# myPlant.net
KiCad netlist of a schematic drawn in EAGLE
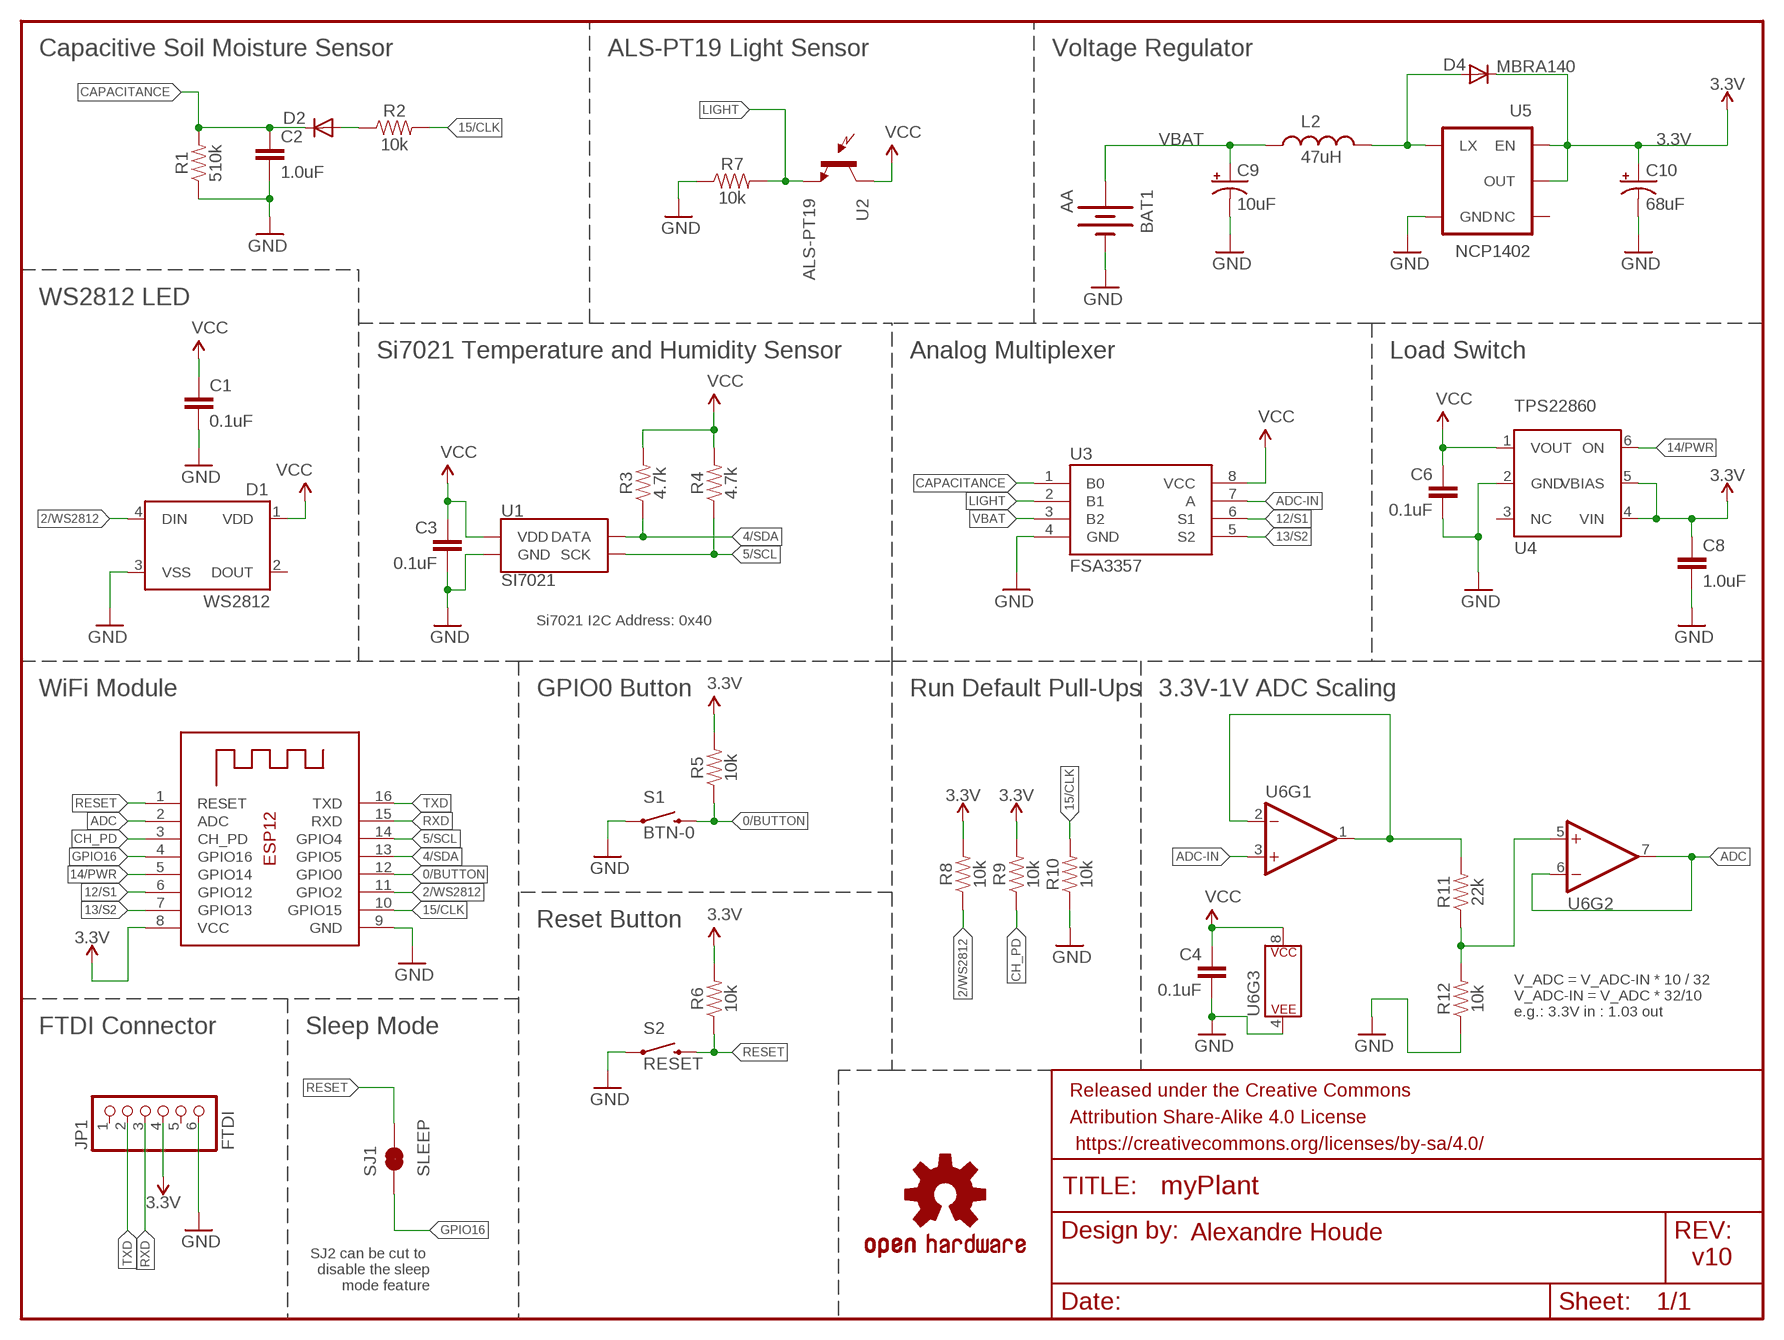
[diagram p0: schematic, sheet 1]

(export (version "E")
  (design (tool "Eeschema 10.0.6"))
  (components
    (comp (ref "BAT1")
      (value "AA")
      (footprint "eagle-import:BATTERY-AA-KIT")
      (libsource (lib "eagle-import") (part "BATTERYAA-KIT"))
    )
    (comp (ref "C1")
      (value "0.1uF")
      (footprint "eagle-import:0603")
      (libsource (lib "eagle-import") (part "0.1UF-0603-25V-(+80/-20%)"))
    )
    (comp (ref "C2")
      (value "1.0uF")
      (footprint "eagle-import:0603")
      (libsource (lib "eagle-import") (part "1.0UF-0603-16V-10%"))
    )
    (comp (ref "C3")
      (value "0.1uF")
      (footprint "eagle-import:0603")
      (libsource (lib "eagle-import") (part "0.1UF-0603-25V-(+80/-20%)"))
    )
    (comp (ref "C4")
      (value "0.1uF")
      (footprint "eagle-import:0603")
      (libsource (lib "eagle-import") (part "0.1UF-0603-25V-(+80/-20%)"))
    )
    (comp (ref "C6")
      (value "0.1uF")
      (footprint "eagle-import:0603")
      (libsource (lib "eagle-import") (part "0.1UF-0603-25V-(+80/-20%)"))
    )
    (comp (ref "C8")
      (value "1.0uF")
      (footprint "eagle-import:0603")
      (libsource (lib "eagle-import") (part "1.0UF-0603-16V-10%"))
    )
    (comp (ref "C9")
      (value "10uF")
      (footprint "eagle-import:EIA3216")
      (libsource (lib "eagle-import") (part "CAP_POL1206"))
    )
    (comp (ref "C10")
      (value "68uF")
      (footprint "eagle-import:EIA3528")
      (libsource (lib "eagle-import") (part "CAP_POL3528"))
    )
    (comp (ref "D1")
      (value "WS2812")
      (footprint "eagle-import:WS2812B")
      (libsource (lib "eagle-import") (part "WS2812B"))
    )
    (comp (ref "D2")
      (value "DIODE-SCHOTTKY_")
      (footprint "eagle-import:SOD-523")
      (libsource (lib "eagle-import") (part "DIODESOD-523"))
    )
    (comp (ref "D4")
      (value "MBRA140")
      (footprint "eagle-import:SMA-DIODE")
      (libsource (lib "eagle-import") (part "DIODESMA"))
    )
    (comp (ref "FRAME1")
      (value "FRAME-LETTER")
      (footprint "eagle-import:CREATIVE_COMMONS")
      (libsource (lib "eagle-import") (part "FRAME-LETTER"))
    )
    (comp (ref "JP1")
      (value "FTDI")
      (footprint "eagle-import:1X06_ROUND_70")
      (libsource (lib "eagle-import") (part "HEADER-1X670MIL"))
    )
    (comp (ref "L2")
      (value "47uH")
      (footprint "eagle-import:CR54")
      (libsource (lib "eagle-import") (part "INDUCTORCR54"))
    )
    (comp (ref "LOGO1")
      (value "OSHW-LOGOM")
      (footprint "eagle-import:OSHW-LOGO-M")
      (libsource (lib "eagle-import") (part "OSHW-LOGOM"))
    )
    (comp (ref "R1")
      (value "510k")
      (footprint "eagle-import:0603")
      (libsource (lib "eagle-import") (part "10KOHM-0603-1/10W-1%"))
    )
    (comp (ref "R2")
      (value "10k")
      (footprint "eagle-import:0603")
      (libsource (lib "eagle-import") (part "10KOHM-0603-1/10W-1%"))
    )
    (comp (ref "R3")
      (value "4.7k")
      (footprint "eagle-import:0603")
      (libsource (lib "eagle-import") (part "4.7KOHM-0603-1/10W-1%"))
    )
    (comp (ref "R4")
      (value "4.7k")
      (footprint "eagle-import:0603")
      (libsource (lib "eagle-import") (part "4.7KOHM-0603-1/10W-1%"))
    )
    (comp (ref "R5")
      (value "10k")
      (footprint "eagle-import:0603")
      (libsource (lib "eagle-import") (part "10KOHM-0603-1/10W-1%"))
    )
    (comp (ref "R6")
      (value "10k")
      (footprint "eagle-import:0603")
      (libsource (lib "eagle-import") (part "10KOHM-0603-1/10W-1%"))
    )
    (comp (ref "R7")
      (value "10k")
      (footprint "eagle-import:0603")
      (libsource (lib "eagle-import") (part "10KOHM-0603-1/10W-1%"))
    )
    (comp (ref "R8")
      (value "10k")
      (footprint "eagle-import:0603")
      (libsource (lib "eagle-import") (part "10KOHM-0603-1/10W-1%"))
    )
    (comp (ref "R9")
      (value "10k")
      (footprint "eagle-import:0603")
      (libsource (lib "eagle-import") (part "10KOHM-0603-1/10W-1%"))
    )
    (comp (ref "R10")
      (value "10k")
      (footprint "eagle-import:0603")
      (libsource (lib "eagle-import") (part "10KOHM-0603-1/10W-1%"))
    )
    (comp (ref "R11")
      (value "22k")
      (footprint "eagle-import:0603")
      (libsource (lib "eagle-import") (part "22KOHM-0603-1/10W-1%"))
    )
    (comp (ref "R12")
      (value "10k")
      (footprint "eagle-import:0603")
      (libsource (lib "eagle-import") (part "10KOHM-0603-1/10W-1%"))
    )
    (comp (ref "S1")
      (value "BTN-0")
      (footprint "eagle-import:TACTILE_SWITCH_SMD_4.6X2.8MM")
      (libsource (lib "eagle-import") (part "SWITCH-MOMENTARY-2SMD-4.6X2.8MM"))
    )
    (comp (ref "S2")
      (value "RESET")
      (footprint "eagle-import:TACTILE_SWITCH_SMD_4.6X2.8MM")
      (libsource (lib "eagle-import") (part "SWITCH-MOMENTARY-2SMD-4.6X2.8MM"))
    )
    (comp (ref "SJ1")
      (value "SLEEP")
      (footprint "eagle-import:PAD-JUMPER-2-NC_BY_TRACE_YES_SILK")
      (libsource (lib "eagle-import") (part "JUMPER-PAD-2-NC_BY_TRACE"))
    )
    (comp (ref "U1")
      (value "SI7021")
      (footprint "eagle-import:DFN-6-3X3-SI7021")
      (libsource (lib "eagle-import") (part "SI7021"))
    )
    (comp (ref "U2")
      (value "ALS-PT19")
      (footprint "eagle-import:ALS-PT19")
      (libsource (lib "eagle-import") (part "LIGHTSENSORALS"))
    )
    (comp (ref "U3")
      (value "FSA3357")
      (footprint "eagle-import:US8")
      (libsource (lib "eagle-import") (part "FSA3357"))
    )
    (comp (ref "U4")
      (value "TPS22860")
      (footprint "eagle-import:SOT23-6")
      (libsource (lib "eagle-import") (part "TPS22860"))
    )
    (comp (ref "U5")
      (value "NCP1402")
      (footprint "eagle-import:SOT23-5")
      (libsource (lib "eagle-import") (part "V_REG_NCP1400SOT23-5"))
    )
    (comp (ref "U6")
      (value "LMV358")
      (footprint "eagle-import:MSOP8")
      (libsource (lib "eagle-import") (part "LMV358"))
    )
    (comp (ref "X1")
      (value "ESP-12")
      (footprint "eagle-import:ESP-12")
      (libsource (lib "eagle-import") (part "ESP-12"))
    )
  )
  (nets
    (net (code "1") (name "0{slash}BUTTON") (class "Default")
      (node (ref "R5") (pin "1") (pinfunction "1_1") (pintype "passive"))
      (node (ref "S1") (pin "3") (pinfunction "2_3") (pintype "passive"))
      (node (ref "S1") (pin "4") (pinfunction "2_4") (pintype "passive"))
      (node (ref "X1") (pin "12") (pinfunction "GPIO0_12") (pintype "bidirectional"))
    )
    (net (code "2") (name "2{slash}WS2812") (class "Default")
      (node (ref "D1") (pin "4") (pinfunction "DIN_4") (pintype "input"))
      (node (ref "R8") (pin "1") (pinfunction "1_1") (pintype "passive"))
      (node (ref "X1") (pin "11") (pinfunction "GPIO2_11") (pintype "bidirectional"))
    )
    (net (code "3") (name "3.3V") (class "Default")
      (node (ref "C10") (pin "A") (pinfunction "+_A") (pintype "passive"))
      (node (ref "C8") (pin "1") (pinfunction "1_1") (pintype "passive"))
      (node (ref "D4") (pin "C") (pinfunction "C_C") (pintype "passive"))
      (node (ref "JP1") (pin "4") (pinfunction "4_4") (pintype "passive"))
      (node (ref "R5") (pin "2") (pinfunction "2_2") (pintype "passive"))
      (node (ref "R6") (pin "2") (pinfunction "2_2") (pintype "passive"))
      (node (ref "R8") (pin "2") (pinfunction "2_2") (pintype "passive"))
      (node (ref "R9") (pin "2") (pinfunction "2_2") (pintype "passive"))
      (node (ref "U4") (pin "4") (pinfunction "VIN_4") (pintype "bidirectional"))
      (node (ref "U4") (pin "5") (pinfunction "VBIAS_5") (pintype "bidirectional"))
      (node (ref "U5") (pin "1") (pinfunction "EN_1") (pintype "input"))
      (node (ref "U5") (pin "2") (pinfunction "OUT_2") (pintype "passive"))
      (node (ref "X1") (pin "8") (pinfunction "VCC_8") (pintype "power_in"))
    )
    (net (code "4") (name "4{slash}SDA") (class "Default")
      (node (ref "R3") (pin "1") (pinfunction "1_1") (pintype "passive"))
      (node (ref "U1") (pin "DATA") (pinfunction "DATA_DATA") (pintype "bidirectional"))
      (node (ref "X1") (pin "13") (pinfunction "GPIO5_13") (pintype "bidirectional"))
    )
    (net (code "5") (name "5{slash}SCL") (class "Default")
      (node (ref "R4") (pin "1") (pinfunction "1_1") (pintype "passive"))
      (node (ref "U1") (pin "SCK") (pinfunction "SCK_SCK") (pintype "input"))
      (node (ref "X1") (pin "14") (pinfunction "GPIO4_14") (pintype "bidirectional"))
    )
    (net (code "6") (name "12{slash}S1") (class "Default")
      (node (ref "U3") (pin "6") (pinfunction "S1_6") (pintype "bidirectional"))
      (node (ref "X1") (pin "6") (pinfunction "GPIO12_6") (pintype "bidirectional"))
    )
    (net (code "7") (name "13{slash}S2") (class "Default")
      (node (ref "U3") (pin "5") (pinfunction "S2_5") (pintype "bidirectional"))
      (node (ref "X1") (pin "7") (pinfunction "GPIO13_7") (pintype "bidirectional"))
    )
    (net (code "8") (name "14{slash}PWR") (class "Default")
      (node (ref "U4") (pin "6") (pinfunction "ON_6") (pintype "bidirectional"))
      (node (ref "X1") (pin "5") (pinfunction "GPIO14_5") (pintype "bidirectional"))
    )
    (net (code "9") (name "15{slash}CLK") (class "Default")
      (node (ref "R10") (pin "2") (pinfunction "2_2") (pintype "passive"))
      (node (ref "R2") (pin "2") (pinfunction "2_2") (pintype "passive"))
      (node (ref "X1") (pin "10") (pinfunction "GPIO15_10") (pintype "bidirectional"))
    )
    (net (code "10") (name "ADC") (class "Default")
      (node (ref "U6") (pin "6") (pinfunction "-IN_6") (pintype "input"))
      (node (ref "U6") (pin "7") (pinfunction "OUT_7") (pintype "output"))
      (node (ref "X1") (pin "2") (pinfunction "ADC_2") (pintype "passive"))
    )
    (net (code "11") (name "ADC-IN") (class "Default")
      (node (ref "U3") (pin "7") (pinfunction "A_7") (pintype "bidirectional"))
      (node (ref "U6") (pin "3") (pinfunction "+IN_3") (pintype "input"))
    )
    (net (code "12") (name "CAPACITANCE") (class "Default")
      (node (ref "C2") (pin "1") (pinfunction "1_1") (pintype "passive"))
      (node (ref "D2") (pin "K") (pinfunction "C_K") (pintype "passive"))
      (node (ref "R1") (pin "2") (pinfunction "2_2") (pintype "passive"))
      (node (ref "U3") (pin "1") (pinfunction "B0_1") (pintype "bidirectional"))
    )
    (net (code "13") (name "CH_PD") (class "Default")
      (node (ref "R9") (pin "1") (pinfunction "1_1") (pintype "passive"))
      (node (ref "X1") (pin "3") (pinfunction "CH_PD_3") (pintype "input"))
    )
    (net (code "14") (name "GND") (class "Default")
      (node (ref "BAT1") (pin "GND@1") (pinfunction "-_GND@1") (pintype "power_in"))
      (node (ref "C1") (pin "2") (pinfunction "2_2") (pintype "passive"))
      (node (ref "C10") (pin "C") (pinfunction "-_C") (pintype "passive"))
      (node (ref "C2") (pin "2") (pinfunction "2_2") (pintype "passive"))
      (node (ref "C3") (pin "2") (pinfunction "2_2") (pintype "passive"))
      (node (ref "C4") (pin "2") (pinfunction "2_2") (pintype "passive"))
      (node (ref "C6") (pin "2") (pinfunction "2_2") (pintype "passive"))
      (node (ref "C8") (pin "2") (pinfunction "2_2") (pintype "passive"))
      (node (ref "C9") (pin "C") (pinfunction "-_C") (pintype "passive"))
      (node (ref "D1") (pin "3") (pinfunction "VSS_3") (pintype "power_in"))
      (node (ref "JP1") (pin "6") (pinfunction "6_6") (pintype "passive"))
      (node (ref "R1") (pin "1") (pinfunction "1_1") (pintype "passive"))
      (node (ref "R10") (pin "1") (pinfunction "1_1") (pintype "passive"))
      (node (ref "R12") (pin "1") (pinfunction "1_1") (pintype "passive"))
      (node (ref "R7") (pin "1") (pinfunction "1_1") (pintype "passive"))
      (node (ref "S1") (pin "1") (pinfunction "1_1") (pintype "passive"))
      (node (ref "S1") (pin "2") (pinfunction "1_2") (pintype "passive"))
      (node (ref "S2") (pin "1") (pinfunction "1_1") (pintype "passive"))
      (node (ref "S2") (pin "2") (pinfunction "1_2") (pintype "passive"))
      (node (ref "U1") (pin "GND") (pinfunction "GND_GND") (pintype "power_in"))
      (node (ref "U3") (pin "4") (pinfunction "GND_4") (pintype "bidirectional"))
      (node (ref "U4") (pin "2") (pinfunction "GND_2") (pintype "bidirectional"))
      (node (ref "U5") (pin "4") (pinfunction "GND_4") (pintype "input"))
      (node (ref "U6") (pin "4") (pinfunction "P$V-_4") (pintype "bidirectional"))
      (node (ref "X1") (pin "9") (pinfunction "GND_9") (pintype "power_in"))
    )
    (net (code "15") (name "GPIO16") (class "Default")
      (node (ref "SJ1") (pin "1") (pinfunction "1_1") (pintype "passive"))
      (node (ref "X1") (pin "4") (pinfunction "GPIO16_4") (pintype "bidirectional"))
    )
    (net (code "16") (name "LIGHT") (class "Default")
      (node (ref "R7") (pin "2") (pinfunction "2_2") (pintype "passive"))
      (node (ref "U2") (pin "E") (pinfunction "E1_E") (pintype "passive"))
      (node (ref "U3") (pin "2") (pinfunction "B1_2") (pintype "bidirectional"))
    )
    (net (code "17") (name "Net-(D2-PadA)") (class "Default")
      (node (ref "D2") (pin "A") (pinfunction "A_A") (pintype "passive"))
      (node (ref "R2") (pin "1") (pinfunction "1_1") (pintype "passive"))
    )
    (net (code "18") (name "Net-(L2-2)") (class "Default")
      (node (ref "D4") (pin "A") (pinfunction "A_A") (pintype "passive"))
      (node (ref "L2") (pin "P$2") (pinfunction "2_P$2") (pintype "passive"))
      (node (ref "U5") (pin "5") (pinfunction "LX_5") (pintype "input"))
    )
    (net (code "19") (name "Net-(U6A--IN)") (class "Default")
      (node (ref "R11") (pin "2") (pinfunction "2_2") (pintype "passive"))
      (node (ref "U6") (pin "1") (pinfunction "OUT_1") (pintype "output"))
      (node (ref "U6") (pin "2") (pinfunction "-IN_2") (pintype "input"))
    )
    (net (code "20") (name "Net-(U6B-+IN)") (class "Default")
      (node (ref "R11") (pin "1") (pinfunction "1_1") (pintype "passive"))
      (node (ref "R12") (pin "2") (pinfunction "2_2") (pintype "passive"))
      (node (ref "U6") (pin "5") (pinfunction "+IN_5") (pintype "input"))
    )
    (net (code "21") (name "RESET") (class "Default")
      (node (ref "R6") (pin "1") (pinfunction "1_1") (pintype "passive"))
      (node (ref "S2") (pin "3") (pinfunction "2_3") (pintype "passive"))
      (node (ref "S2") (pin "4") (pinfunction "2_4") (pintype "passive"))
      (node (ref "SJ1") (pin "2") (pinfunction "2_2") (pintype "passive"))
      (node (ref "X1") (pin "1") (pinfunction "RESET_1") (pintype "input"))
    )
    (net (code "22") (name "RXD") (class "Default")
      (node (ref "JP1") (pin "3") (pinfunction "3_3") (pintype "passive"))
      (node (ref "X1") (pin "15") (pinfunction "RXD_15") (pintype "input"))
    )
    (net (code "23") (name "TXD") (class "Default")
      (node (ref "JP1") (pin "2") (pinfunction "2_2") (pintype "passive"))
      (node (ref "X1") (pin "16") (pinfunction "TXD_16") (pintype "output"))
    )
    (net (code "24") (name "VBAT") (class "Default")
      (node (ref "BAT1") (pin "PWR@1") (pinfunction "+_PWR@1") (pintype "power_in"))
      (node (ref "C9") (pin "A") (pinfunction "+_A") (pintype "passive"))
      (node (ref "L2") (pin "P$1") (pinfunction "1_P$1") (pintype "passive"))
      (node (ref "U3") (pin "3") (pinfunction "B2_3") (pintype "bidirectional"))
    )
    (net (code "25") (name "VCC") (class "Default")
      (node (ref "C1") (pin "1") (pinfunction "1_1") (pintype "passive"))
      (node (ref "C3") (pin "1") (pinfunction "1_1") (pintype "passive"))
      (node (ref "C4") (pin "1") (pinfunction "1_1") (pintype "passive"))
      (node (ref "C6") (pin "1") (pinfunction "1_1") (pintype "passive"))
      (node (ref "D1") (pin "1") (pinfunction "VDD_1") (pintype "power_in"))
      (node (ref "R3") (pin "2") (pinfunction "2_2") (pintype "passive"))
      (node (ref "R4") (pin "2") (pinfunction "2_2") (pintype "passive"))
      (node (ref "U1") (pin "VDD") (pinfunction "VDD_VDD") (pintype "power_in"))
      (node (ref "U2") (pin "C") (pinfunction "C1_C") (pintype "passive"))
      (node (ref "U3") (pin "8") (pinfunction "VCC_8") (pintype "bidirectional"))
      (node (ref "U4") (pin "1") (pinfunction "VOUT_1") (pintype "bidirectional"))
      (node (ref "U6") (pin "8") (pinfunction "P$V+_8") (pintype "bidirectional"))
    )
    (net (code "26") (name "unconnected-(D1-DOUT-Pad2)") (class "Default")
      (node (ref "D1") (pin "2") (pinfunction "DOUT_2") (pintype "output"))
    )
    (net (code "27") (name "unconnected-(JP1-Pad1)") (class "Default")
      (node (ref "JP1") (pin "1") (pinfunction "1_1") (pintype "passive"))
    )
    (net (code "28") (name "unconnected-(JP1-Pad5)") (class "Default")
      (node (ref "JP1") (pin "5") (pinfunction "5_5") (pintype "passive"))
    )
    (net (code "29") (name "unconnected-(U4-NC-Pad3)") (class "Default")
      (node (ref "U4") (pin "3") (pinfunction "NC_3") (pintype "bidirectional"))
    )
    (net (code "30") (name "unconnected-(U5-NC-Pad3)") (class "Default")
      (node (ref "U5") (pin "3") (pinfunction "NC_3") (pintype "input"))
    )
  )
)
